# fully_diff_1_7.net
KiCad netlist of a schematic drawn in EAGLE
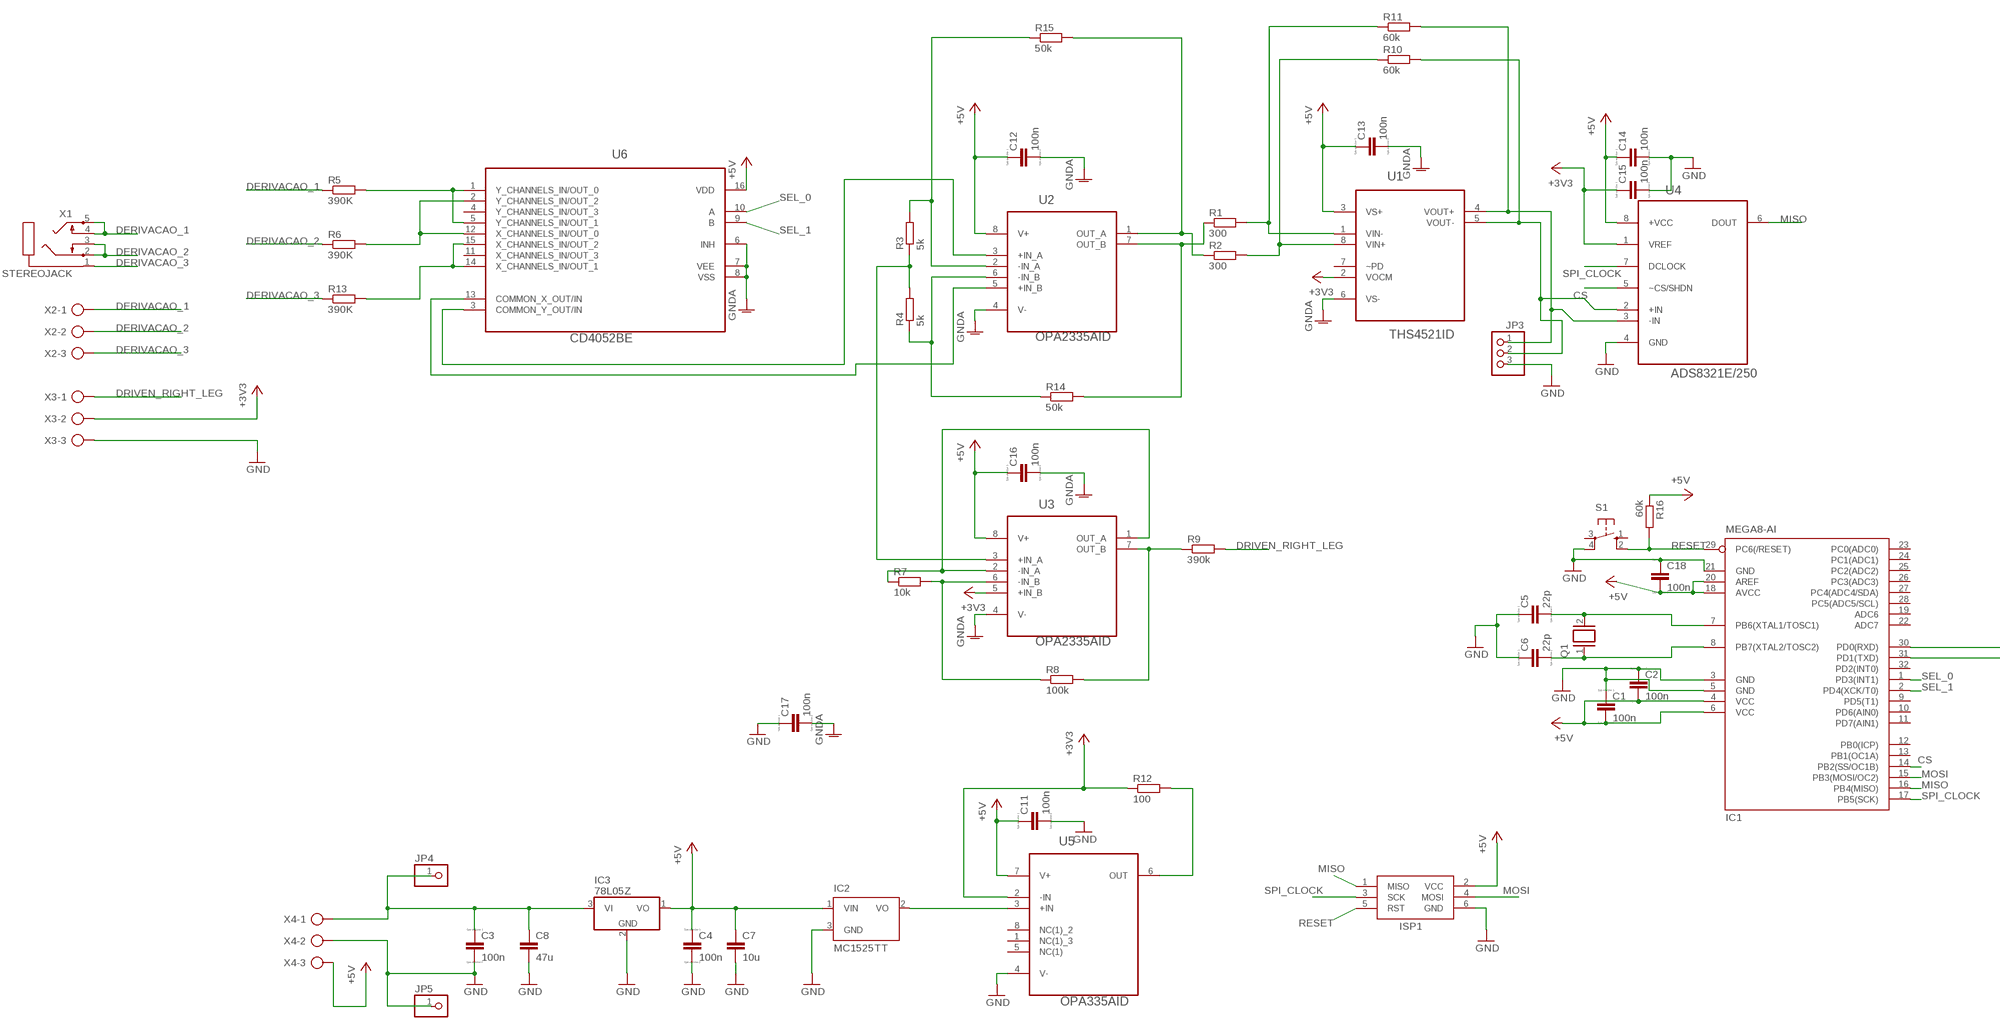
[diagram p0: schematic, sheet 1, part 1 of 2]
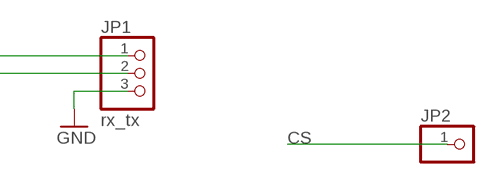
[diagram p1: schematic, sheet 1, part 2 of 2]

(export (version "E")
  (design (tool "Eeschema 10.0.6"))
  (components
    (comp (ref "C1")
      (value "100n")
      (footprint "eagle-import:C1206")
      (libsource (lib "eagle-import") (part "CC1206"))
    )
    (comp (ref "C2")
      (value "100n")
      (footprint "eagle-import:C1206")
      (libsource (lib "eagle-import") (part "CC1206"))
    )
    (comp (ref "C3")
      (value "100n")
      (footprint "eagle-import:C1206")
      (libsource (lib "eagle-import") (part "CC1206"))
    )
    (comp (ref "C4")
      (value "100n")
      (footprint "eagle-import:C1206")
      (libsource (lib "eagle-import") (part "CC1206"))
    )
    (comp (ref "C5")
      (value "22p")
      (footprint "eagle-import:C1206")
      (libsource (lib "eagle-import") (part "CC1206"))
    )
    (comp (ref "C6")
      (value "22p")
      (footprint "eagle-import:C1206")
      (libsource (lib "eagle-import") (part "CC1206"))
    )
    (comp (ref "C7")
      (value "10u")
      (footprint "eagle-import:C025-030X050")
      (libsource (lib "eagle-import") (part "C-EU025-030X050"))
    )
    (comp (ref "C8")
      (value "47u")
      (footprint "eagle-import:C025-030X050")
      (libsource (lib "eagle-import") (part "C-EU025-030X050"))
    )
    (comp (ref "C11")
      (value "100n")
      (footprint "eagle-import:C1206")
      (libsource (lib "eagle-import") (part "CC1206"))
    )
    (comp (ref "C12")
      (value "100n")
      (footprint "eagle-import:C1206")
      (libsource (lib "eagle-import") (part "CC1206"))
    )
    (comp (ref "C13")
      (value "100n")
      (footprint "eagle-import:C1206")
      (libsource (lib "eagle-import") (part "CC1206"))
    )
    (comp (ref "C14")
      (value "100n")
      (footprint "eagle-import:C1206")
      (libsource (lib "eagle-import") (part "CC1206"))
    )
    (comp (ref "C15")
      (value "100n")
      (footprint "eagle-import:C1206")
      (libsource (lib "eagle-import") (part "CC1206"))
    )
    (comp (ref "C16")
      (value "100n")
      (footprint "eagle-import:C1206")
      (libsource (lib "eagle-import") (part "CC1206"))
    )
    (comp (ref "C17")
      (value "100n")
      (footprint "eagle-import:C1206")
      (libsource (lib "eagle-import") (part "CC1206"))
    )
    (comp (ref "C18")
      (value "100n")
      (footprint "eagle-import:C1206")
      (libsource (lib "eagle-import") (part "CC1206"))
    )
    (comp (ref "IC1")
      (value "MEGA8-AI")
      (footprint "eagle-import:TQFP32-08")
      (fields (field (name "MPN") "ATMEGA8-16AU"))
      (libsource (lib "eagle-import") (part "MEGA8-AI"))
    )
    (comp (ref "IC2")
      (value "MC1525TT")
      (footprint "eagle-import:SOT23")
      (libsource (lib "eagle-import") (part "MC15TT25"))
    )
    (comp (ref "IC3")
      (value "78L05Z")
      (footprint "eagle-import:TO92")
      (libsource (lib "eagle-import") (part "78ZL05"))
    )
    (comp (ref "ISP1")
      (value "AVRISP-6")
      (footprint "eagle-import:AVRISP")
      (libsource (lib "eagle-import") (part "AVRISP-6"))
    )
    (comp (ref "JP1")
      (value "rx_tx")
      (footprint "eagle-import:1X03")
      (libsource (lib "eagle-import") (part "PINHD-1X3"))
    )
    (comp (ref "JP2")
      (value "PINHD-1X1")
      (footprint "eagle-import:1X01")
      (libsource (lib "eagle-import") (part "PINHD-1X1"))
    )
    (comp (ref "JP3")
      (value "PINHD-1X3")
      (footprint "eagle-import:1X03")
      (libsource (lib "eagle-import") (part "PINHD-1X3"))
    )
    (comp (ref "JP4")
      (value "PINHD-1X1")
      (footprint "eagle-import:1X01")
      (libsource (lib "eagle-import") (part "PINHD-1X1"))
    )
    (comp (ref "JP5")
      (value "PINHD-1X1")
      (footprint "eagle-import:1X01")
      (libsource (lib "eagle-import") (part "PINHD-1X1"))
    )
    (comp (ref "Q1")
      (value "XTAL/S")
      (footprint "eagle-import:QS")
      (libsource (lib "eagle-import") (part "XTAL/S"))
    )
    (comp (ref "R1")
      (value "300")
      (footprint "eagle-import:R1206")
      (libsource (lib "eagle-import") (part "R-EU_R1206"))
    )
    (comp (ref "R2")
      (value "300")
      (footprint "eagle-import:R1206")
      (libsource (lib "eagle-import") (part "R-EU_R1206"))
    )
    (comp (ref "R3")
      (value "5k")
      (footprint "eagle-import:R1206")
      (libsource (lib "eagle-import") (part "R-EU_R1206"))
    )
    (comp (ref "R4")
      (value "5k")
      (footprint "eagle-import:R1206")
      (libsource (lib "eagle-import") (part "R-EU_R1206"))
    )
    (comp (ref "R5")
      (value "390K")
      (footprint "eagle-import:R1206")
      (libsource (lib "eagle-import") (part "R-EU_R1206"))
    )
    (comp (ref "R6")
      (value "390K")
      (footprint "eagle-import:R1206")
      (libsource (lib "eagle-import") (part "R-EU_R1206"))
    )
    (comp (ref "R7")
      (value "10k")
      (footprint "eagle-import:R1206")
      (libsource (lib "eagle-import") (part "R-EU_R1206"))
    )
    (comp (ref "R8")
      (value "100k")
      (footprint "eagle-import:R1206")
      (libsource (lib "eagle-import") (part "R-EU_R1206"))
    )
    (comp (ref "R9")
      (value "390k")
      (footprint "eagle-import:R1206")
      (libsource (lib "eagle-import") (part "R-EU_R1206"))
    )
    (comp (ref "R10")
      (value "60k")
      (footprint "eagle-import:R1206")
      (libsource (lib "eagle-import") (part "R-EU_R1206"))
    )
    (comp (ref "R11")
      (value "60k")
      (footprint "eagle-import:R1206")
      (libsource (lib "eagle-import") (part "R-EU_R1206"))
    )
    (comp (ref "R12")
      (value "100")
      (footprint "eagle-import:R1206")
      (libsource (lib "eagle-import") (part "R-EU_R1206"))
    )
    (comp (ref "R13")
      (value "390K")
      (footprint "eagle-import:R1206")
      (libsource (lib "eagle-import") (part "R-EU_R1206"))
    )
    (comp (ref "R14")
      (value "50k")
      (footprint "eagle-import:R1206")
      (libsource (lib "eagle-import") (part "R-EU_R1206"))
    )
    (comp (ref "R15")
      (value "50k")
      (footprint "eagle-import:R1206")
      (libsource (lib "eagle-import") (part "R-EU_R1206"))
    )
    (comp (ref "R16")
      (value "60k")
      (footprint "eagle-import:R1206")
      (libsource (lib "eagle-import") (part "R-EU_R1206"))
    )
    (comp (ref "S1")
      (value "10-XX")
      (footprint "eagle-import:B3F-10XX")
      (fields (field (name "MPN") "B3F-1000"))
      (libsource (lib "eagle-import") (part "10-XX"))
    )
    (comp (ref "U1")
      (value "THS4521ID")
      (footprint "eagle-import:SOIC127P600X175-8N")
      (libsource (lib "eagle-import") (part "THS4521ID"))
    )
    (comp (ref "U2")
      (value "OPA2335AID")
      (footprint "eagle-import:SOIC127P600X175-8N")
      (libsource (lib "eagle-import") (part "OPA2335AID"))
    )
    (comp (ref "U3")
      (value "OPA2335AID")
      (footprint "eagle-import:SOIC127P600X175-8N")
      (libsource (lib "eagle-import") (part "OPA2335AID"))
    )
    (comp (ref "U4")
      (value "ADS8321E/250")
      (footprint "eagle-import:SOP65P490X110-8N")
      (libsource (lib "eagle-import") (part "ADS8321E/250"))
    )
    (comp (ref "U5")
      (value "OPA335AID")
      (footprint "eagle-import:SOIC127P600X175-8N")
      (libsource (lib "eagle-import") (part "OPA335AID"))
    )
    (comp (ref "U6")
      (value "CD4052BE")
      (footprint "eagle-import:DIP254P762X508-16")
      (libsource (lib "eagle-import") (part "CD4052BE"))
    )
    (comp (ref "X1")
      (value "STEREOJACK")
      (footprint "eagle-import:STX3100")
      (libsource (lib "eagle-import") (part "STEREOJACK"))
    )
    (comp (ref "X2")
      (value "AK300/3")
      (footprint "eagle-import:AK300_3")
      (libsource (lib "eagle-import") (part "AK300/3"))
    )
    (comp (ref "X3")
      (value "AK300/3")
      (footprint "eagle-import:AK300_3")
      (libsource (lib "eagle-import") (part "AK300/3"))
    )
    (comp (ref "X4")
      (value "AK300/3")
      (footprint "eagle-import:AK300_3")
      (libsource (lib "eagle-import") (part "AK300/3"))
    )
  )
  (nets
    (net (code "1") (name "+3V3") (class "Default")
      (node (ref "C15") (pin "1") (pinfunction "1_1") (pintype "passive"))
      (node (ref "R12") (pin "1") (pinfunction "1_1") (pintype "passive"))
      (node (ref "U1") (pin "2") (pinfunction "VOCM_2") (pintype "input"))
      (node (ref "U3") (pin "5") (pinfunction "+IN_B_5") (pintype "input"))
      (node (ref "U4") (pin "1") (pinfunction "VREF_1") (pintype "input"))
      (node (ref "U5") (pin "2") (pinfunction "-IN_2") (pintype "input"))
      (node (ref "X3") (pin "2") (pinfunction "KL_2") (pintype "passive"))
    )
    (net (code "2") (name "+5V") (class "Default")
      (node (ref "C1") (pin "2") (pinfunction "2_2") (pintype "passive"))
      (node (ref "C11") (pin "1") (pinfunction "1_1") (pintype "passive"))
      (node (ref "C12") (pin "1") (pinfunction "1_1") (pintype "passive"))
      (node (ref "C13") (pin "1") (pinfunction "1_1") (pintype "passive"))
      (node (ref "C14") (pin "1") (pinfunction "1_1") (pintype "passive"))
      (node (ref "C16") (pin "1") (pinfunction "1_1") (pintype "passive"))
      (node (ref "C18") (pin "2") (pinfunction "2_2") (pintype "passive"))
      (node (ref "C2") (pin "2") (pinfunction "2_2") (pintype "passive"))
      (node (ref "C4") (pin "1") (pinfunction "1_1") (pintype "passive"))
      (node (ref "C7") (pin "1") (pinfunction "1_1") (pintype "passive"))
      (node (ref "IC1") (pin "18") (pinfunction "AVCC_18") (pintype "power_in"))
      (node (ref "IC1") (pin "20") (pinfunction "AREF_20") (pintype "passive"))
      (node (ref "IC1") (pin "4") (pinfunction "VCC_4") (pintype "power_in"))
      (node (ref "IC1") (pin "6") (pinfunction "VCC_6") (pintype "power_in"))
      (node (ref "IC2") (pin "1") (pinfunction "VIN_1") (pintype "input"))
      (node (ref "IC3") (pin "1") (pinfunction "VO_1") (pintype "passive"))
      (node (ref "ISP1") (pin "2") (pinfunction "VCC_2") (pintype "power_in"))
      (node (ref "R16") (pin "1") (pinfunction "1_1") (pintype "passive"))
      (node (ref "U1") (pin "3") (pinfunction "VS+_3") (pintype "power_in"))
      (node (ref "U2") (pin "8") (pinfunction "V+_8") (pintype "power_in"))
      (node (ref "U3") (pin "8") (pinfunction "V+_8") (pintype "power_in"))
      (node (ref "U4") (pin "8") (pinfunction "+VCC_8") (pintype "power_in"))
      (node (ref "U5") (pin "7") (pinfunction "V+_7") (pintype "power_in"))
      (node (ref "U6") (pin "16") (pinfunction "VDD_16") (pintype "power_in"))
      (node (ref "X4") (pin "3") (pinfunction "KL_3") (pintype "passive"))
    )
    (net (code "3") (name "/CS") (class "Default")
      (node (ref "IC1") (pin "14") (pinfunction "PB2(SS/OC1B)_14") (pintype "bidirectional"))
      (node (ref "JP2") (pin "1") (pinfunction "1_1") (pintype "passive"))
      (node (ref "U4") (pin "5") (pinfunction "~{CS/SHDN}_5") (pintype "input"))
    )
    (net (code "4") (name "/DERIVACAO_1") (class "Default")
      (node (ref "R5") (pin "1") (pinfunction "1_1") (pintype "passive"))
      (node (ref "X1") (pin "4") (pinfunction "4_4") (pintype "passive"))
      (node (ref "X1") (pin "5") (pinfunction "5_5") (pintype "passive"))
      (node (ref "X2") (pin "1") (pinfunction "KL_1") (pintype "passive"))
    )
    (net (code "5") (name "/DERIVACAO_2") (class "Default")
      (node (ref "R6") (pin "1") (pinfunction "1_1") (pintype "passive"))
      (node (ref "X1") (pin "2") (pinfunction "2_2") (pintype "passive"))
      (node (ref "X1") (pin "3") (pinfunction "3_3") (pintype "passive"))
      (node (ref "X2") (pin "2") (pinfunction "KL_2") (pintype "passive"))
    )
    (net (code "6") (name "/DERIVACAO_3") (class "Default")
      (node (ref "R13") (pin "1") (pinfunction "1_1") (pintype "passive"))
      (node (ref "X1") (pin "1") (pinfunction "1_1") (pintype "passive"))
      (node (ref "X2") (pin "3") (pinfunction "KL_3") (pintype "passive"))
    )
    (net (code "7") (name "/DRIVEN_RIGHT_LEG") (class "Default")
      (node (ref "R9") (pin "2") (pinfunction "2_2") (pintype "passive"))
      (node (ref "X3") (pin "1") (pinfunction "KL_1") (pintype "passive"))
    )
    (net (code "8") (name "/MISO") (class "Default")
      (node (ref "IC1") (pin "16") (pinfunction "PB4(MISO)_16") (pintype "bidirectional"))
      (node (ref "ISP1") (pin "1") (pinfunction "MISO_1") (pintype "input"))
      (node (ref "U4") (pin "6") (pinfunction "DOUT_6") (pintype "output"))
    )
    (net (code "9") (name "/MOSI") (class "Default")
      (node (ref "IC1") (pin "15") (pinfunction "PB3(MOSI/OC2)_15") (pintype "bidirectional"))
      (node (ref "ISP1") (pin "4") (pinfunction "MOSI_4") (pintype "output"))
    )
    (net (code "10") (name "/RESET") (class "Default")
      (node (ref "IC1") (pin "29") (pinfunction "PC6(/RESET)_29") (pintype "bidirectional"))
      (node (ref "ISP1") (pin "5") (pinfunction "RST_5") (pintype "output"))
      (node (ref "R16") (pin "2") (pinfunction "2_2") (pintype "passive"))
      (node (ref "S1") (pin "2") (pinfunction "S1_2") (pintype "passive"))
    )
    (net (code "11") (name "/SEL_0") (class "Default")
      (node (ref "IC1") (pin "1") (pinfunction "PD3(INT1)_1") (pintype "bidirectional"))
      (node (ref "U6") (pin "10") (pinfunction "A_10") (pintype "input"))
    )
    (net (code "12") (name "/SEL_1") (class "Default")
      (node (ref "IC1") (pin "2") (pinfunction "PD4(XCK/T0)_2") (pintype "bidirectional"))
      (node (ref "U6") (pin "9") (pinfunction "B_9") (pintype "input"))
    )
    (net (code "13") (name "/SPI_CLOCK") (class "Default")
      (node (ref "IC1") (pin "17") (pinfunction "PB5(SCK)_17") (pintype "bidirectional"))
      (node (ref "ISP1") (pin "3") (pinfunction "SCK_3") (pintype "output"))
      (node (ref "U4") (pin "7") (pinfunction "DCLOCK_7") (pintype "input"))
    )
    (net (code "14") (name "GND") (class "Default")
      (node (ref "C1") (pin "1") (pinfunction "1_1") (pintype "passive"))
      (node (ref "C11") (pin "2") (pinfunction "2_2") (pintype "passive"))
      (node (ref "C14") (pin "2") (pinfunction "2_2") (pintype "passive"))
      (node (ref "C15") (pin "2") (pinfunction "2_2") (pintype "passive"))
      (node (ref "C17") (pin "1") (pinfunction "1_1") (pintype "passive"))
      (node (ref "C18") (pin "1") (pinfunction "1_1") (pintype "passive"))
      (node (ref "C2") (pin "1") (pinfunction "1_1") (pintype "passive"))
      (node (ref "C3") (pin "2") (pinfunction "2_2") (pintype "passive"))
      (node (ref "C4") (pin "2") (pinfunction "2_2") (pintype "passive"))
      (node (ref "C5") (pin "1") (pinfunction "1_1") (pintype "passive"))
      (node (ref "C6") (pin "1") (pinfunction "1_1") (pintype "passive"))
      (node (ref "C7") (pin "2") (pinfunction "2_2") (pintype "passive"))
      (node (ref "C8") (pin "2") (pinfunction "2_2") (pintype "passive"))
      (node (ref "IC1") (pin "21") (pinfunction "GND_21") (pintype "power_in"))
      (node (ref "IC1") (pin "3") (pinfunction "GND_3") (pintype "power_in"))
      (node (ref "IC1") (pin "5") (pinfunction "GND_5") (pintype "power_in"))
      (node (ref "IC2") (pin "3") (pinfunction "GND_3") (pintype "passive"))
      (node (ref "IC3") (pin "2") (pinfunction "GND_2") (pintype "passive"))
      (node (ref "ISP1") (pin "6") (pinfunction "GND_6") (pintype "power_in"))
      (node (ref "JP1") (pin "3") (pinfunction "3_3") (pintype "passive"))
      (node (ref "JP3") (pin "3") (pinfunction "3_3") (pintype "passive"))
      (node (ref "JP5") (pin "1") (pinfunction "1_1") (pintype "passive"))
      (node (ref "S1") (pin "4") (pinfunction "P1_4") (pintype "passive"))
      (node (ref "U4") (pin "4") (pinfunction "GND_4") (pintype "passive"))
      (node (ref "U5") (pin "4") (pinfunction "V-_4") (pintype "power_in"))
      (node (ref "X3") (pin "3") (pinfunction "KL_3") (pintype "passive"))
      (node (ref "X4") (pin "2") (pinfunction "KL_2") (pintype "passive"))
    )
    (net (code "15") (name "GNDA") (class "Default")
      (node (ref "C12") (pin "2") (pinfunction "2_2") (pintype "passive"))
      (node (ref "C13") (pin "2") (pinfunction "2_2") (pintype "passive"))
      (node (ref "C16") (pin "2") (pinfunction "2_2") (pintype "passive"))
      (node (ref "C17") (pin "2") (pinfunction "2_2") (pintype "passive"))
      (node (ref "U1") (pin "6") (pinfunction "VS-_6") (pintype "power_in"))
      (node (ref "U2") (pin "4") (pinfunction "V-_4") (pintype "power_in"))
      (node (ref "U3") (pin "4") (pinfunction "V-_4") (pintype "power_in"))
      (node (ref "U6") (pin "6") (pinfunction "INH_6") (pintype "input"))
      (node (ref "U6") (pin "7") (pinfunction "VEE_7") (pintype "power_in"))
      (node (ref "U6") (pin "8") (pinfunction "VSS_8") (pintype "power_in"))
    )
    (net (code "16") (name "Net-(IC1-PB6(XTAL1{slash}TOSC1))") (class "Default")
      (node (ref "C5") (pin "2") (pinfunction "2_2") (pintype "passive"))
      (node (ref "IC1") (pin "7") (pinfunction "PB6(XTAL1/TOSC1)_7") (pintype "bidirectional"))
      (node (ref "Q1") (pin "2") (pinfunction "2_2") (pintype "passive"))
    )
    (net (code "17") (name "Net-(IC1-PB7(XTAL2{slash}TOSC2))") (class "Default")
      (node (ref "C6") (pin "2") (pinfunction "2_2") (pintype "passive"))
      (node (ref "IC1") (pin "8") (pinfunction "PB7(XTAL2/TOSC2)_8") (pintype "bidirectional"))
      (node (ref "Q1") (pin "1") (pinfunction "1_1") (pintype "passive"))
    )
    (net (code "18") (name "Net-(IC1-PD0(RXD))") (class "Default")
      (node (ref "IC1") (pin "30") (pinfunction "PD0(RXD)_30") (pintype "bidirectional"))
      (node (ref "JP1") (pin "1") (pinfunction "1_1") (pintype "passive"))
    )
    (net (code "19") (name "Net-(IC1-PD1(TXD))") (class "Default")
      (node (ref "IC1") (pin "31") (pinfunction "PD1(TXD)_31") (pintype "bidirectional"))
      (node (ref "JP1") (pin "2") (pinfunction "2_2") (pintype "passive"))
    )
    (net (code "20") (name "Net-(IC2-VO)") (class "Default")
      (node (ref "IC2") (pin "2") (pinfunction "VO_2") (pintype "output"))
      (node (ref "U5") (pin "3") (pinfunction "+IN_3") (pintype "input"))
    )
    (net (code "21") (name "Net-(IC3-VI)") (class "Default")
      (node (ref "C3") (pin "1") (pinfunction "1_1") (pintype "passive"))
      (node (ref "C8") (pin "1") (pinfunction "1_1") (pintype "passive"))
      (node (ref "IC3") (pin "3") (pinfunction "VI_3") (pintype "input"))
      (node (ref "JP4") (pin "1") (pinfunction "1_1") (pintype "passive"))
      (node (ref "X4") (pin "1") (pinfunction "KL_1") (pintype "passive"))
    )
    (net (code "22") (name "Net-(U1-VIN+)") (class "Default")
      (node (ref "R10") (pin "1") (pinfunction "1_1") (pintype "passive"))
      (node (ref "R2") (pin "2") (pinfunction "2_2") (pintype "passive"))
      (node (ref "U1") (pin "8") (pinfunction "VIN+_8") (pintype "input"))
    )
    (net (code "23") (name "Net-(U1-VIN-)") (class "Default")
      (node (ref "R1") (pin "2") (pinfunction "2_2") (pintype "passive"))
      (node (ref "R11") (pin "1") (pinfunction "1_1") (pintype "passive"))
      (node (ref "U1") (pin "1") (pinfunction "VIN-_1") (pintype "input"))
    )
    (net (code "24") (name "Net-(U1-VOUT+)") (class "Default")
      (node (ref "JP3") (pin "1") (pinfunction "1_1") (pintype "passive"))
      (node (ref "R11") (pin "2") (pinfunction "2_2") (pintype "passive"))
      (node (ref "U1") (pin "4") (pinfunction "VOUT+_4") (pintype "output"))
      (node (ref "U4") (pin "3") (pinfunction "-IN_3") (pintype "input"))
    )
    (net (code "25") (name "Net-(U1-VOUT-)") (class "Default")
      (node (ref "JP3") (pin "2") (pinfunction "2_2") (pintype "passive"))
      (node (ref "R10") (pin "2") (pinfunction "2_2") (pintype "passive"))
      (node (ref "U1") (pin "5") (pinfunction "VOUT-_5") (pintype "output"))
      (node (ref "U4") (pin "2") (pinfunction "+IN_2") (pintype "input"))
    )
    (net (code "26") (name "Net-(U2-+IN_A)") (class "Default")
      (node (ref "U2") (pin "3") (pinfunction "+IN_A_3") (pintype "input"))
      (node (ref "U6") (pin "3") (pinfunction "COMMON_Y_OUT/IN_3") (pintype "bidirectional"))
    )
    (net (code "27") (name "Net-(U2-+IN_B)") (class "Default")
      (node (ref "U2") (pin "5") (pinfunction "+IN_B_5") (pintype "input"))
      (node (ref "U6") (pin "13") (pinfunction "COMMON_X_OUT/IN_13") (pintype "bidirectional"))
    )
    (net (code "28") (name "Net-(U2--IN_A)") (class "Default")
      (node (ref "R15") (pin "1") (pinfunction "1_1") (pintype "passive"))
      (node (ref "R3") (pin "2") (pinfunction "2_2") (pintype "passive"))
      (node (ref "U2") (pin "2") (pinfunction "-IN_A_2") (pintype "input"))
    )
    (net (code "29") (name "Net-(U2--IN_B)") (class "Default")
      (node (ref "R14") (pin "1") (pinfunction "1_1") (pintype "passive"))
      (node (ref "R4") (pin "1") (pinfunction "1_1") (pintype "passive"))
      (node (ref "U2") (pin "6") (pinfunction "-IN_B_6") (pintype "input"))
    )
    (net (code "30") (name "Net-(U2-OUT_A)") (class "Default")
      (node (ref "R15") (pin "2") (pinfunction "2_2") (pintype "passive"))
      (node (ref "R2") (pin "1") (pinfunction "1_1") (pintype "passive"))
      (node (ref "U2") (pin "1") (pinfunction "OUT_A_1") (pintype "output"))
    )
    (net (code "31") (name "Net-(U2-OUT_B)") (class "Default")
      (node (ref "R1") (pin "1") (pinfunction "1_1") (pintype "passive"))
      (node (ref "R14") (pin "2") (pinfunction "2_2") (pintype "passive"))
      (node (ref "U2") (pin "7") (pinfunction "OUT_B_7") (pintype "output"))
    )
    (net (code "32") (name "Net-(U3-+IN_A)") (class "Default")
      (node (ref "R3") (pin "1") (pinfunction "1_1") (pintype "passive"))
      (node (ref "R4") (pin "2") (pinfunction "2_2") (pintype "passive"))
      (node (ref "U3") (pin "3") (pinfunction "+IN_A_3") (pintype "input"))
    )
    (net (code "33") (name "Net-(U3--IN_A)") (class "Default")
      (node (ref "R7") (pin "1") (pinfunction "1_1") (pintype "passive"))
      (node (ref "U3") (pin "1") (pinfunction "OUT_A_1") (pintype "output"))
      (node (ref "U3") (pin "2") (pinfunction "-IN_A_2") (pintype "input"))
    )
    (net (code "34") (name "Net-(U3--IN_B)") (class "Default")
      (node (ref "R7") (pin "2") (pinfunction "2_2") (pintype "passive"))
      (node (ref "R8") (pin "1") (pinfunction "1_1") (pintype "passive"))
      (node (ref "U3") (pin "6") (pinfunction "-IN_B_6") (pintype "input"))
    )
    (net (code "35") (name "Net-(U3-OUT_B)") (class "Default")
      (node (ref "R8") (pin "2") (pinfunction "2_2") (pintype "passive"))
      (node (ref "R9") (pin "1") (pinfunction "1_1") (pintype "passive"))
      (node (ref "U3") (pin "7") (pinfunction "OUT_B_7") (pintype "output"))
    )
    (net (code "36") (name "Net-(U5-OUT)") (class "Default")
      (node (ref "R12") (pin "2") (pinfunction "2_2") (pintype "passive"))
      (node (ref "U5") (pin "6") (pinfunction "OUT_6") (pintype "output"))
    )
    (net (code "37") (name "Net-(U6-X_CHANNELS_IN{slash}OUT_0)") (class "Default")
      (node (ref "R6") (pin "2") (pinfunction "2_2") (pintype "passive"))
      (node (ref "U6") (pin "12") (pinfunction "X_CHANNELS_IN/OUT_0_12") (pintype "bidirectional"))
      (node (ref "U6") (pin "2") (pinfunction "Y_CHANNELS_IN/OUT_2_2") (pintype "bidirectional"))
    )
    (net (code "38") (name "Net-(U6-X_CHANNELS_IN{slash}OUT_1)") (class "Default")
      (node (ref "R13") (pin "2") (pinfunction "2_2") (pintype "passive"))
      (node (ref "U6") (pin "14") (pinfunction "X_CHANNELS_IN/OUT_1_14") (pintype "bidirectional"))
      (node (ref "U6") (pin "15") (pinfunction "X_CHANNELS_IN/OUT_2_15") (pintype "bidirectional"))
    )
    (net (code "39") (name "Net-(U6-Y_CHANNELS_IN{slash}OUT_0)") (class "Default")
      (node (ref "R5") (pin "2") (pinfunction "2_2") (pintype "passive"))
      (node (ref "U6") (pin "1") (pinfunction "Y_CHANNELS_IN/OUT_0_1") (pintype "bidirectional"))
      (node (ref "U6") (pin "5") (pinfunction "Y_CHANNELS_IN/OUT_1_5") (pintype "bidirectional"))
    )
    (net (code "40") (name "unconnected-(IC1-ADC6-Pad19)") (class "Default")
      (node (ref "IC1") (pin "19") (pinfunction "ADC6_19") (pintype "bidirectional"))
    )
    (net (code "41") (name "unconnected-(IC1-ADC7-Pad22)") (class "Default")
      (node (ref "IC1") (pin "22") (pinfunction "ADC7_22") (pintype "bidirectional"))
    )
    (net (code "42") (name "unconnected-(IC1-PB0(ICP)-Pad12)") (class "Default")
      (node (ref "IC1") (pin "12") (pinfunction "PB0(ICP)_12") (pintype "bidirectional"))
    )
    (net (code "43") (name "unconnected-(IC1-PB1(OC1A)-Pad13)") (class "Default")
      (node (ref "IC1") (pin "13") (pinfunction "PB1(OC1A)_13") (pintype "bidirectional"))
    )
    (net (code "44") (name "unconnected-(IC1-PC0(ADC0)-Pad23)") (class "Default")
      (node (ref "IC1") (pin "23") (pinfunction "PC0(ADC0)_23") (pintype "bidirectional"))
    )
    (net (code "45") (name "unconnected-(IC1-PC1(ADC1)-Pad24)") (class "Default")
      (node (ref "IC1") (pin "24") (pinfunction "PC1(ADC1)_24") (pintype "bidirectional"))
    )
    (net (code "46") (name "unconnected-(IC1-PC2(ADC2)-Pad25)") (class "Default")
      (node (ref "IC1") (pin "25") (pinfunction "PC2(ADC2)_25") (pintype "bidirectional"))
    )
    (net (code "47") (name "unconnected-(IC1-PC3(ADC3)-Pad26)") (class "Default")
      (node (ref "IC1") (pin "26") (pinfunction "PC3(ADC3)_26") (pintype "bidirectional"))
    )
    (net (code "48") (name "unconnected-(IC1-PC4(ADC4{slash}SDA)-Pad27)") (class "Default")
      (node (ref "IC1") (pin "27") (pinfunction "PC4(ADC4/SDA)_27") (pintype "bidirectional"))
    )
    (net (code "49") (name "unconnected-(IC1-PC5(ADC5{slash}SCL)-Pad28)") (class "Default")
      (node (ref "IC1") (pin "28") (pinfunction "PC5(ADC5/SCL)_28") (pintype "bidirectional"))
    )
    (net (code "50") (name "unconnected-(IC1-PD2(INT0)-Pad32)") (class "Default")
      (node (ref "IC1") (pin "32") (pinfunction "PD2(INT0)_32") (pintype "bidirectional"))
    )
    (net (code "51") (name "unconnected-(IC1-PD5(T1)-Pad9)") (class "Default")
      (node (ref "IC1") (pin "9") (pinfunction "PD5(T1)_9") (pintype "bidirectional"))
    )
    (net (code "52") (name "unconnected-(IC1-PD6(AIN0)-Pad10)") (class "Default")
      (node (ref "IC1") (pin "10") (pinfunction "PD6(AIN0)_10") (pintype "bidirectional"))
    )
    (net (code "53") (name "unconnected-(IC1-PD7(AIN1)-Pad11)") (class "Default")
      (node (ref "IC1") (pin "11") (pinfunction "PD7(AIN1)_11") (pintype "bidirectional"))
    )
    (net (code "54") (name "unconnected-(S1-P-Pad3)") (class "Default")
      (node (ref "S1") (pin "3") (pinfunction "P_3") (pintype "passive"))
    )
    (net (code "55") (name "unconnected-(S1-S-Pad1)") (class "Default")
      (node (ref "S1") (pin "1") (pinfunction "S_1") (pintype "passive"))
    )
    (net (code "56") (name "unconnected-(U1-~{PD}-Pad7)") (class "Default")
      (node (ref "U1") (pin "7") (pinfunction "~{PD}_7") (pintype "input"))
    )
    (net (code "57") (name "unconnected-(U5-NC(1)-Pad5)") (class "Default")
      (node (ref "U5") (pin "5") (pinfunction "NC(1)_5") (pintype "no_connect"))
    )
    (net (code "58") (name "unconnected-(U5-NC(1)_2-Pad8)") (class "Default")
      (node (ref "U5") (pin "8") (pinfunction "NC(1)_2_8") (pintype "no_connect"))
    )
    (net (code "59") (name "unconnected-(U5-NC(1)_3-Pad1)") (class "Default")
      (node (ref "U5") (pin "1") (pinfunction "NC(1)_3_1") (pintype "no_connect"))
    )
    (net (code "60") (name "unconnected-(U6-X_CHANNELS_IN{slash}OUT_3-Pad11)") (class "Default")
      (node (ref "U6") (pin "11") (pinfunction "X_CHANNELS_IN/OUT_3_11") (pintype "bidirectional"))
    )
    (net (code "61") (name "unconnected-(U6-Y_CHANNELS_IN{slash}OUT_3-Pad4)") (class "Default")
      (node (ref "U6") (pin "4") (pinfunction "Y_CHANNELS_IN/OUT_3_4") (pintype "bidirectional"))
    )
  )
)
